# ProPrj_24v_5v_2024-09-12.net
KiCad netlist of a schematic drawn in EasyEDA Pro
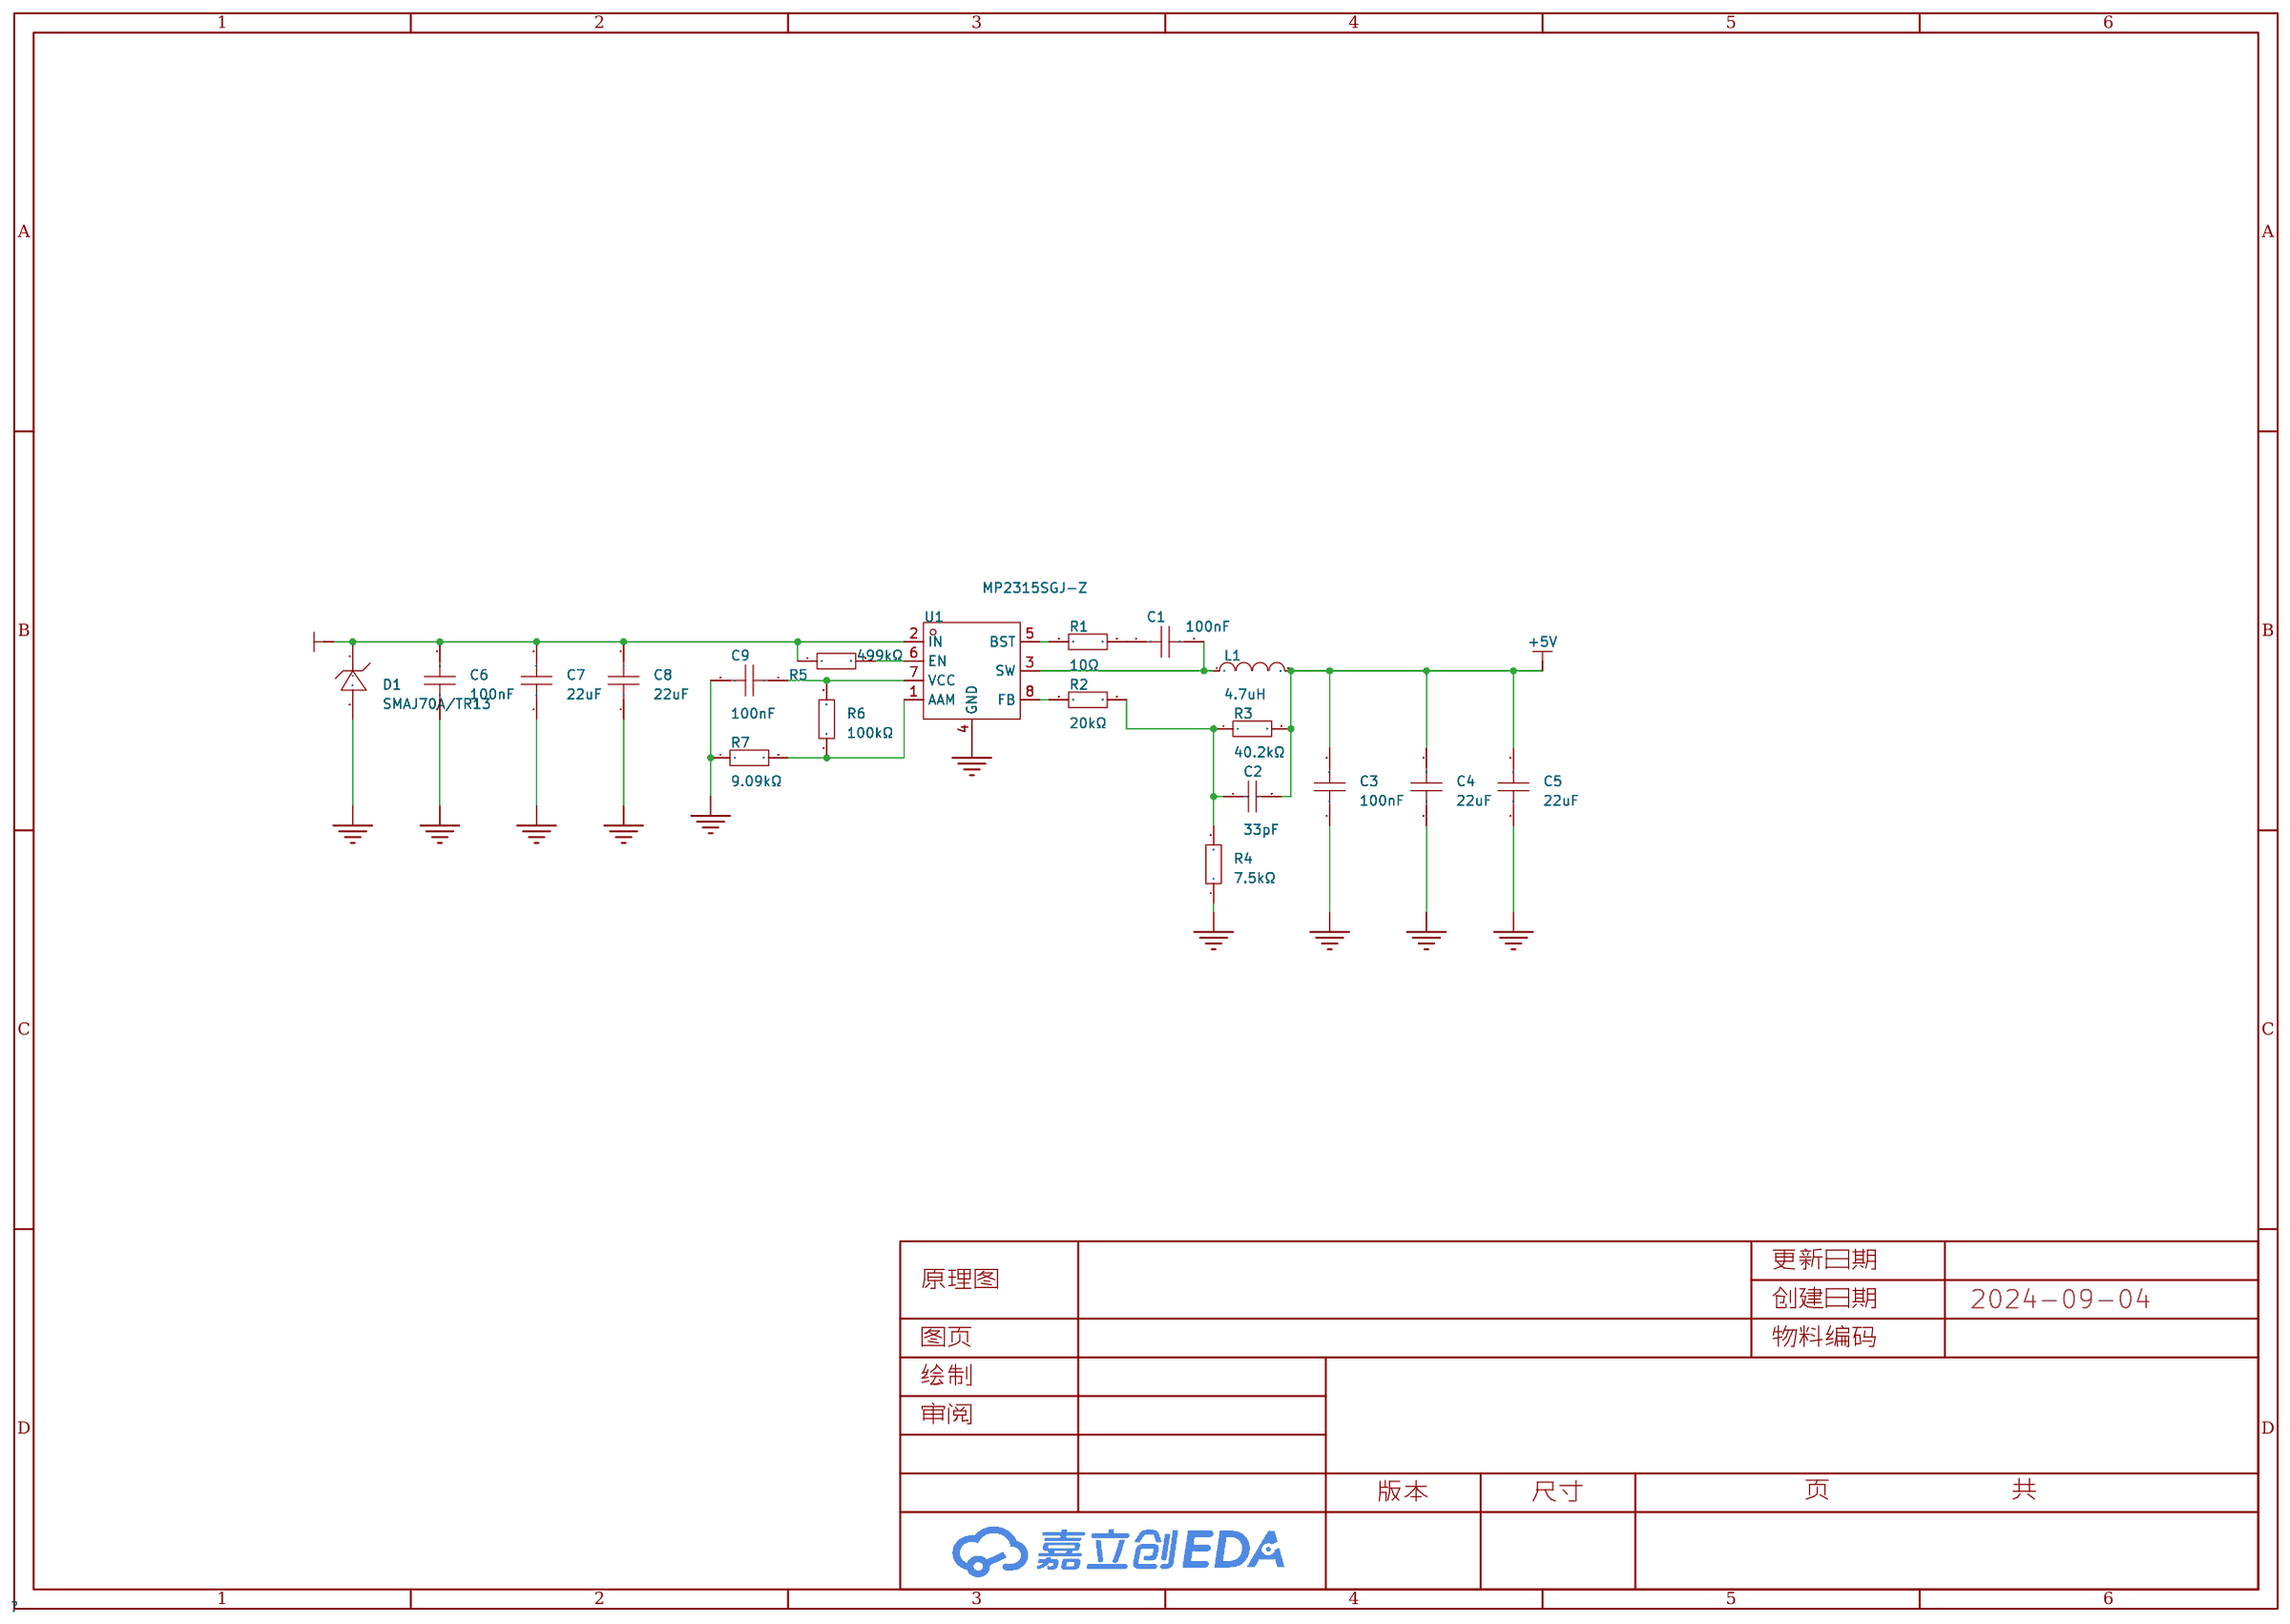
[diagram p0: schematic sheet]

(export (version "E")
  (design (tool "Eeschema 10.0.6"))
  (components
    (comp (ref "C1")
      (value "100nF")
      (footprint "easyedapro:C0603")
      (description "容值:100nF;精度:±10%;额定电压:50V;材质(温度系数):X7R;")
      (fields
        (field (name "Manufacturer Part") "CGA0603X7R104K500JT")
        (field (name "Manufacturer") "HRE(芯声)")
      )
      (libsource (lib "easyedapro") (part "CGA0603X7R104K500JT"))
    )
    (comp (ref "C2")
      (value "33pF")
      (footprint "easyedapro:C0603")
      (description "容值:33pF;精度:±5%;额定电压:50V;材质(温度系数):C0G;")
      (fields
        (field (name "Manufacturer Part") "CL10C330JB8NNNC")
        (field (name "Manufacturer") "SAMSUNG(三星)")
      )
      (libsource (lib "easyedapro") (part "CL10C330JB8NNNC"))
    )
    (comp (ref "C3")
      (value "100nF")
      (footprint "easyedapro:C0603")
      (description "容值:100nF;精度:±10%;额定电压:50V;材质(温度系数):X7R;")
      (fields
        (field (name "Manufacturer Part") "CGA0603X7R104K500JT")
        (field (name "Manufacturer") "HRE(芯声)")
      )
      (libsource (lib "easyedapro") (part "CGA0603X7R104K500JT"))
    )
    (comp (ref "C4")
      (value "22uF")
      (footprint "easyedapro:C0603")
      (description "容值:22uF;精度:±20%;额定电压:16V;材质(温度系数):X5R;")
      (fields
        (field (name "Manufacturer Part") "CGA0603X5R226M160JT")
        (field (name "Manufacturer") "HRE(芯声)")
      )
      (libsource (lib "easyedapro") (part "CGA0603X5R226M160JT"))
    )
    (comp (ref "C5")
      (value "22uF")
      (footprint "easyedapro:C0603")
      (description "容值:22uF;精度:±20%;额定电压:16V;材质(温度系数):X5R;")
      (fields
        (field (name "Manufacturer Part") "CGA0603X5R226M160JT")
        (field (name "Manufacturer") "HRE(芯声)")
      )
      (libsource (lib "easyedapro") (part "CGA0603X5R226M160JT"))
    )
    (comp (ref "C6")
      (value "100nF")
      (footprint "easyedapro:C0603")
      (description "容值:100nF;精度:±10%;额定电压:50V;材质(温度系数):X7R;")
      (fields
        (field (name "Manufacturer Part") "CGA0603X7R104K500JT")
        (field (name "Manufacturer") "HRE(芯声)")
      )
      (libsource (lib "easyedapro") (part "CGA0603X7R104K500JT"))
    )
    (comp (ref "C7")
      (value "22uF")
      (footprint "easyedapro:C0603")
      (description "容值:22uF;精度:±20%;额定电压:16V;材质(温度系数):X5R;")
      (fields
        (field (name "Manufacturer Part") "CGA0603X5R226M160JT")
        (field (name "Manufacturer") "HRE(芯声)")
      )
      (libsource (lib "easyedapro") (part "CGA0603X5R226M160JT"))
    )
    (comp (ref "C8")
      (value "22uF")
      (footprint "easyedapro:C0603")
      (description "容值:22uF;精度:±20%;额定电压:16V;材质(温度系数):X5R;")
      (fields
        (field (name "Manufacturer Part") "CGA0603X5R226M160JT")
        (field (name "Manufacturer") "HRE(芯声)")
      )
      (libsource (lib "easyedapro") (part "CGA0603X5R226M160JT"))
    )
    (comp (ref "C9")
      (value "100nF")
      (footprint "easyedapro:C0603")
      (description "容值:100nF;精度:±10%;额定电压:50V;材质(温度系数):X7R;")
      (fields
        (field (name "Manufacturer Part") "CGA0603X7R104K500JT")
        (field (name "Manufacturer") "HRE(芯声)")
      )
      (libsource (lib "easyedapro") (part "CGA0603X7R104K500JT"))
    )
    (comp (ref "D1")
      (value "SMAJ70A/TR13")
      (footprint "easyedapro:SMA_L4.3-W2.6-LS5.1-RD")
      (description "反向截止电压(Vrwm):70V;最大钳位电压:113V;峰值脉冲电流(Ipp)@10/1000us:3.5A;峰值脉冲功率(Ppp)@10/1000us:400W;击穿电压:77.8V;")
      (fields (field (name "Manufacturer") "Brightking(君耀电子)"))
      (libsource (lib "easyedapro") (part "SMAJ70A"))
    )
    (comp (ref "L1")
      (value "4.7uH")
      (footprint "easyedapro:IND-SMD_L5.4-W5.2_FXL0530")
      (description "电感值:4.7uH;精度:±20%;额定电流:4.5A;饱和电流(Isat):5A;类型:一体成型电感;")
      (fields (field (name "Manufacturer Part") "FXL0530-4R7-M") (field (name "Manufacturer") "cjiang(长江微电)"))
      (libsource (lib "easyedapro") (part "FXL0530-4R7-M"))
    )
    (comp (ref "R1")
      (value "10Ω")
      (footprint "easyedapro:R0603")
      (description "电阻类型:厚膜电阻;阻值:10Ω;精度:±1%;功率:100mW;最大工作电压:75V;温度系数:±400ppm/°C;")
      (fields
        (field (name "Manufacturer Part") "0603WAF100JT5E")
        (field (name "Manufacturer") "UNI-ROYAL(厚声)")
      )
      (libsource (lib "easyedapro") (part "0603WAF100JT5E"))
    )
    (comp (ref "R2")
      (value "20kΩ")
      (footprint "easyedapro:R0603")
      (description "电阻类型:厚膜电阻;阻值:20kΩ;精度:±1%;功率:100mW;最大工作电压:75V;温度系数:±100ppm/°C;")
      (fields
        (field (name "Manufacturer Part") "0603WAF2002T5E")
        (field (name "Manufacturer") "UNI-ROYAL(厚声)")
      )
      (libsource (lib "easyedapro") (part "0603WAF2002T5E"))
    )
    (comp (ref "R3")
      (value "40.2kΩ")
      (footprint "easyedapro:R0603")
      (description "电阻类型:厚膜电阻;阻值:40.2kΩ;精度:±1%;功率:100mW;最大工作电压:75V;温度系数:±100ppm/°C;")
      (fields
        (field (name "Manufacturer Part") "0603WAF4022T5E")
        (field (name "Manufacturer") "UNI-ROYAL(厚声)")
      )
      (libsource (lib "easyedapro") (part "0603WAF4022T5E"))
    )
    (comp (ref "R4")
      (value "7.5kΩ")
      (footprint "easyedapro:R0603")
      (description "电阻类型:厚膜电阻;阻值:7.5kΩ;精度:±1%;功率:100mW;最大工作电压:75V;温度系数:±100ppm/°C;")
      (fields
        (field (name "Manufacturer Part") "0603WAF7501T5E")
        (field (name "Manufacturer") "UNI-ROYAL(厚声)")
      )
      (libsource (lib "easyedapro") (part "0603WAF7501T5E"))
    )
    (comp (ref "R5")
      (value "499kΩ")
      (footprint "easyedapro:R0603")
      (description "电阻类型:厚膜电阻;阻值:499kΩ;精度:±1%;功率:100mW;最大工作电压:75V;温度系数:±100ppm/°C;")
      (fields
        (field (name "Manufacturer Part") "0603WAF4993T5E")
        (field (name "Manufacturer") "UNI-ROYAL(厚声)")
      )
      (libsource (lib "easyedapro") (part "0603WAF4993T5E"))
    )
    (comp (ref "R6")
      (value "100kΩ")
      (footprint "easyedapro:R0603")
      (description "电阻类型:厚膜电阻;阻值:100kΩ;精度:±1%;功率:100mW;最大工作电压:75V;温度系数:±100ppm/°C;")
      (fields (field (name "Manufacturer Part") "RC0603FR-07100KL") (field (name "Manufacturer") "YAGEO(国巨)"))
      (libsource (lib "easyedapro") (part "RC0603FR-07100KL"))
    )
    (comp (ref "R7")
      (value "9.09kΩ")
      (footprint "easyedapro:R0603")
      (description "电阻类型:厚膜电阻;阻值:9.09kΩ;精度:±1%;功率:100mW;最大工作电压:75V;温度系数:±100ppm/°C;")
      (fields
        (field (name "Manufacturer Part") "0603WAF9091T5E")
        (field (name "Manufacturer") "UNI-ROYAL(厚声)")
      )
      (libsource (lib "easyedapro") (part "0603WAF9091T5E"))
    )
    (comp (ref "U1")
      (value "MP2315SGJ-Z")
      (footprint "easyedapro:TSOT-23-8_L2.9-W1.6-P0.65-LS2.8-BL")
      (description "功能类型:降压型;输出类型:可调;输入电压:4.5V~24V;输出电压:800mV~22.8V;输出电流:3A;")
      (fields (field (name "Manufacturer") "MPS(芯源)"))
      (libsource (lib "easyedapro") (part "MP2315SGJ-Z"))
    )
  )
  (nets
    (net (code "1") (name "+5V") (class "Default")
      (node (ref "C2") (pin "2") (pinfunction "2_2") (pintype "input"))
      (node (ref "C3") (pin "2") (pinfunction "2_2") (pintype "unspecified"))
      (node (ref "C4") (pin "2") (pinfunction "2_2") (pintype "unspecified"))
      (node (ref "C5") (pin "2") (pinfunction "2_2") (pintype "unspecified"))
      (node (ref "L1") (pin "2") (pinfunction "2_2") (pintype "unspecified"))
      (node (ref "R3") (pin "2") (pinfunction "2_2") (pintype "input"))
    )
    (net (code "2") (name "24V") (class "Default")
      (node (ref "C6") (pin "2") (pinfunction "2_2") (pintype "unspecified"))
      (node (ref "C7") (pin "2") (pinfunction "2_2") (pintype "unspecified"))
      (node (ref "C8") (pin "2") (pinfunction "2_2") (pintype "unspecified"))
      (node (ref "D1") (pin "1") (pinfunction "1_1") (pintype "input"))
      (node (ref "R5") (pin "1") (pinfunction "1_1") (pintype "input"))
      (node (ref "U1") (pin "2") (pinfunction "IN_2") (pintype "unspecified"))
    )
    (net (code "3") (name "GND") (class "Default")
      (node (ref "C3") (pin "1") (pinfunction "1_1") (pintype "unspecified"))
      (node (ref "C4") (pin "1") (pinfunction "1_1") (pintype "unspecified"))
      (node (ref "C5") (pin "1") (pinfunction "1_1") (pintype "unspecified"))
      (node (ref "C6") (pin "1") (pinfunction "1_1") (pintype "unspecified"))
      (node (ref "C7") (pin "1") (pinfunction "1_1") (pintype "unspecified"))
      (node (ref "C8") (pin "1") (pinfunction "1_1") (pintype "unspecified"))
      (node (ref "C9") (pin "2") (pinfunction "2_2") (pintype "unspecified"))
      (node (ref "D1") (pin "2") (pinfunction "2_2") (pintype "input"))
      (node (ref "R4") (pin "1") (pinfunction "1_1") (pintype "input"))
      (node (ref "R7") (pin "1") (pinfunction "1_1") (pintype "input"))
      (node (ref "U1") (pin "4") (pinfunction "GND_4") (pintype "unspecified"))
    )
    (net (code "4") (name "Net-(C1-Pad1)") (class "Default")
      (node (ref "C1") (pin "1") (pinfunction "1_1") (pintype "unspecified"))
      (node (ref "R1") (pin "2") (pinfunction "2_2") (pintype "input"))
    )
    (net (code "5") (name "Net-(C2-Pad1)") (class "Default")
      (node (ref "C2") (pin "1") (pinfunction "1_1") (pintype "input"))
      (node (ref "R2") (pin "2") (pinfunction "2_2") (pintype "input"))
      (node (ref "R3") (pin "1") (pinfunction "1_1") (pintype "input"))
      (node (ref "R4") (pin "2") (pinfunction "2_2") (pintype "input"))
    )
    (net (code "6") (name "Net-(U1-AAM)") (class "Default")
      (node (ref "R6") (pin "1") (pinfunction "1_1") (pintype "unspecified"))
      (node (ref "R7") (pin "2") (pinfunction "2_2") (pintype "input"))
      (node (ref "U1") (pin "1") (pinfunction "AAM_1") (pintype "unspecified"))
    )
    (net (code "7") (name "Net-(U1-BST)") (class "Default")
      (node (ref "R1") (pin "1") (pinfunction "1_1") (pintype "input"))
      (node (ref "U1") (pin "5") (pinfunction "BST_5") (pintype "unspecified"))
    )
    (net (code "8") (name "Net-(U1-EN)") (class "Default")
      (node (ref "R5") (pin "2") (pinfunction "2_2") (pintype "input"))
      (node (ref "U1") (pin "6") (pinfunction "EN_6") (pintype "unspecified"))
    )
    (net (code "9") (name "Net-(U1-FB)") (class "Default")
      (node (ref "R2") (pin "1") (pinfunction "1_1") (pintype "input"))
      (node (ref "U1") (pin "8") (pinfunction "FB_8") (pintype "unspecified"))
    )
    (net (code "10") (name "Net-(U1-SW)") (class "Default")
      (node (ref "C1") (pin "2") (pinfunction "2_2") (pintype "unspecified"))
      (node (ref "L1") (pin "1") (pinfunction "1_1") (pintype "unspecified"))
      (node (ref "U1") (pin "3") (pinfunction "SW_3") (pintype "unspecified"))
    )
    (net (code "11") (name "Net-(U1-VCC)") (class "Default")
      (node (ref "C9") (pin "1") (pinfunction "1_1") (pintype "unspecified"))
      (node (ref "R6") (pin "2") (pinfunction "2_2") (pintype "unspecified"))
      (node (ref "U1") (pin "7") (pinfunction "VCC_7") (pintype "unspecified"))
    )
  )
)
